# PCB-BI8-3x1.net
KiCad netlist of a schematic drawn in EAGLE
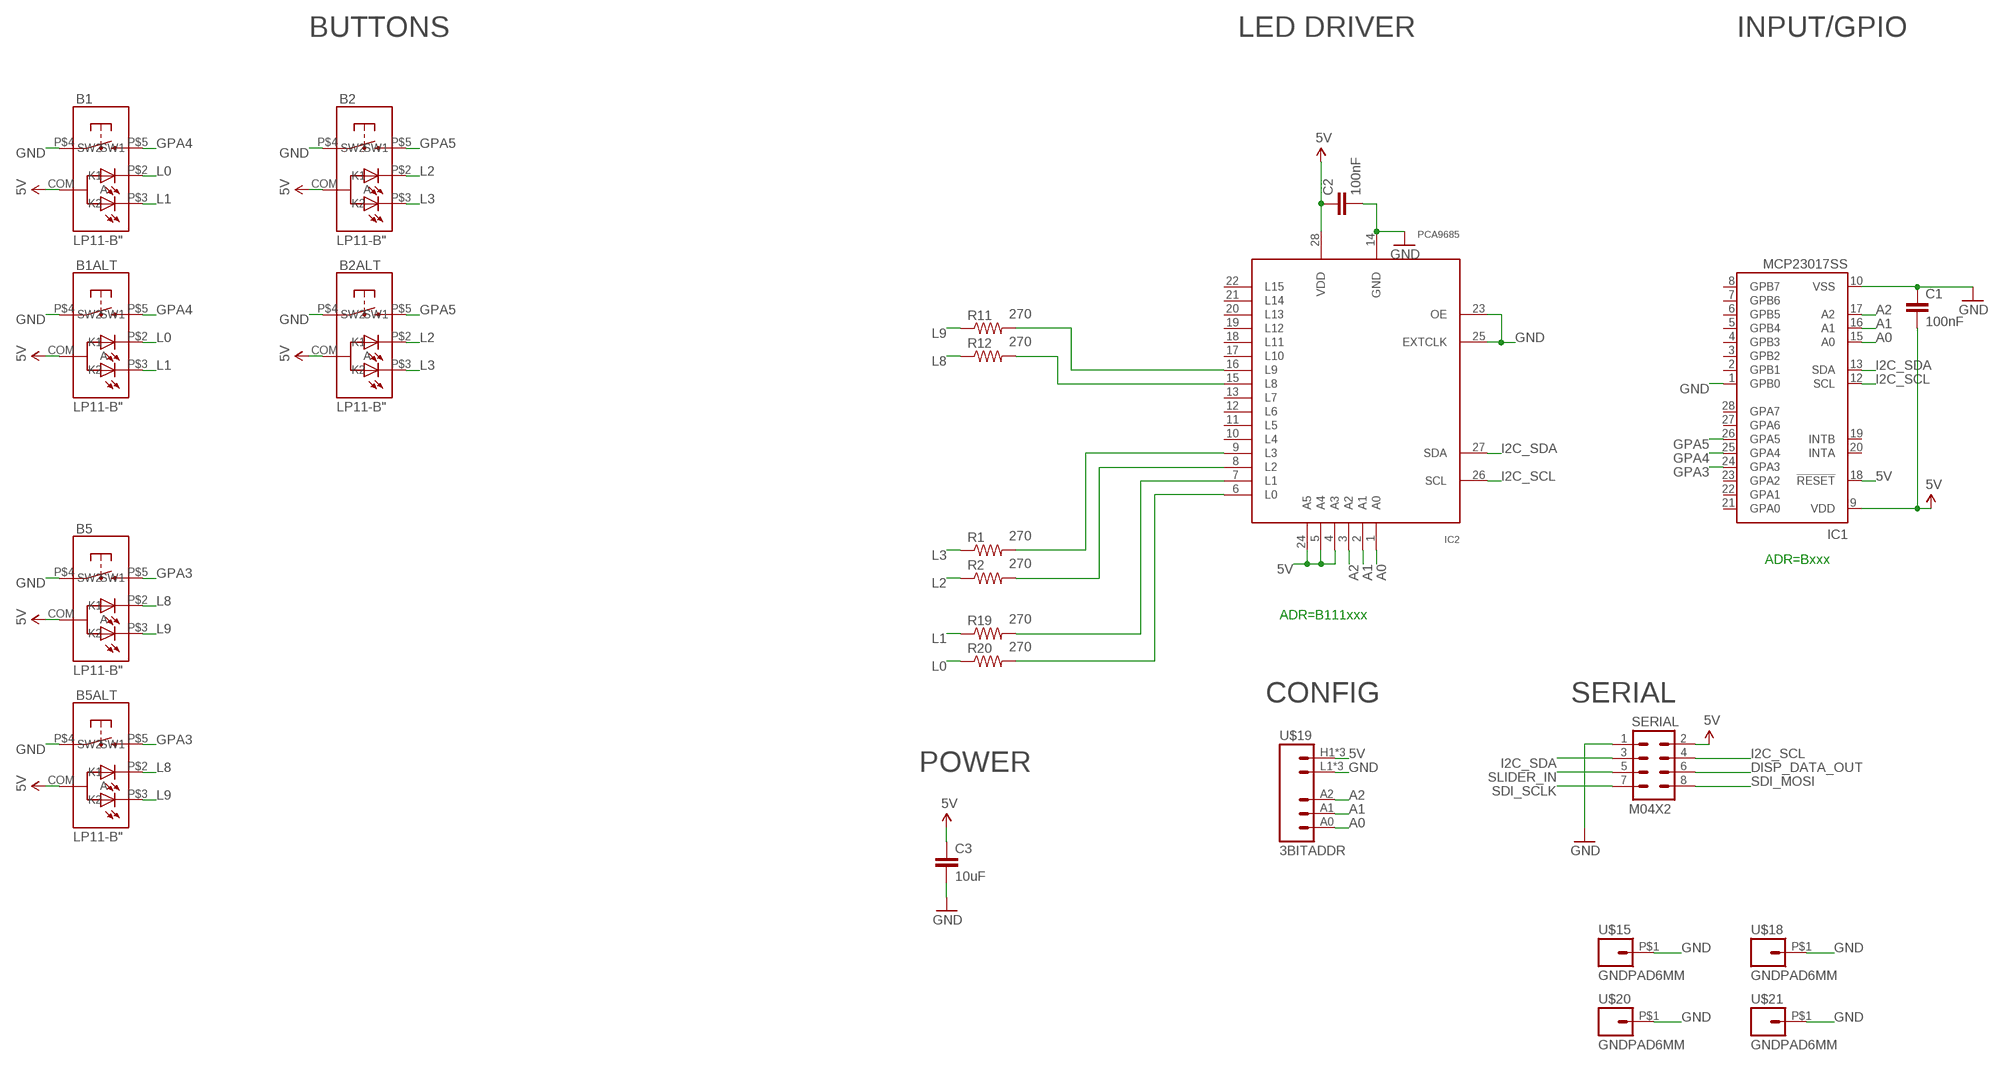
[diagram p0: schematic, sheet 1]

(export (version "E")
  (design (tool "Eeschema 10.0.6"))
  (components
    (comp (ref "B1")
      (value "LP11-B\"")
      (footprint "eagle-import:LP11")
      (libsource (lib "eagle-import") (part "LP11-B{dblquote}"))
    )
    (comp (ref "B1ALT")
      (value "LP11-B\"")
      (footprint "eagle-import:LP11")
      (libsource (lib "eagle-import") (part "LP11-B{dblquote}"))
    )
    (comp (ref "B2")
      (value "LP11-B\"")
      (footprint "eagle-import:LP11")
      (libsource (lib "eagle-import") (part "LP11-B{dblquote}"))
    )
    (comp (ref "B2ALT")
      (value "LP11-B\"")
      (footprint "eagle-import:LP11")
      (libsource (lib "eagle-import") (part "LP11-B{dblquote}"))
    )
    (comp (ref "B5")
      (value "LP11-B\"")
      (footprint "eagle-import:LP11")
      (libsource (lib "eagle-import") (part "LP11-B{dblquote}"))
    )
    (comp (ref "B5ALT")
      (value "LP11-B\"")
      (footprint "eagle-import:LP11")
      (libsource (lib "eagle-import") (part "LP11-B{dblquote}"))
    )
    (comp (ref "C1")
      (value "100nF")
      (footprint "eagle-import:0603-CAP")
      (libsource (lib "eagle-import") (part "CAP0603-CAP"))
    )
    (comp (ref "C2")
      (value "100nF")
      (footprint "eagle-import:0603-CAP")
      (libsource (lib "eagle-import") (part "CAP0603-CAP"))
    )
    (comp (ref "C3")
      (value "10uF")
      (footprint "eagle-import:0805")
      (libsource (lib "eagle-import") (part "CAP0805"))
    )
    (comp (ref "IC1")
      (value "MCP23017SS")
      (footprint "eagle-import:SSOP28")
      (fields
        (field (name "MF") "MICROCHIP")
        (field (name "MPN") "MCP23017-E/SS")
        (field (name "MPN_1") "MCP23017-E/SS")
        (field (name "OC_FARNELL") "1467674")
        (field (name "OC_NEWARK") "31K2960")
      )
      (libsource (lib "eagle-import") (part "MCP23017SS"))
    )
    (comp (ref "IC2")
      (value "PCA9685")
      (footprint "eagle-import:TSSOP28")
      (libsource (lib "eagle-import") (part "PCA9685"))
    )
    (comp (ref "R1")
      (value "270")
      (footprint "eagle-import:0603-RES")
      (libsource (lib "eagle-import") (part "RESISTOR0603-RES"))
    )
    (comp (ref "R2")
      (value "270")
      (footprint "eagle-import:0603-RES")
      (libsource (lib "eagle-import") (part "RESISTOR0603-RES"))
    )
    (comp (ref "R11")
      (value "270")
      (footprint "eagle-import:0603-RES")
      (libsource (lib "eagle-import") (part "RESISTOR0603-RES"))
    )
    (comp (ref "R12")
      (value "270")
      (footprint "eagle-import:0603-RES")
      (libsource (lib "eagle-import") (part "RESISTOR0603-RES"))
    )
    (comp (ref "R19")
      (value "270")
      (footprint "eagle-import:0603-RES")
      (libsource (lib "eagle-import") (part "RESISTOR0603-RES"))
    )
    (comp (ref "R20")
      (value "270")
      (footprint "eagle-import:0603-RES")
      (libsource (lib "eagle-import") (part "RESISTOR0603-RES"))
    )
    (comp (ref "SERIAL")
      (value "M04X2")
      (footprint "eagle-import:2X4")
      (libsource (lib "eagle-import") (part "M04X2"))
    )
    (comp (ref "U$15")
      (value "GNDPAD6MM")
      (footprint "eagle-import:3.2MMPAD6MM")
      (libsource (lib "eagle-import") (part "GNDPAD6MM"))
    )
    (comp (ref "U$18")
      (value "GNDPAD6MM")
      (footprint "eagle-import:3.2MMPAD6MM")
      (libsource (lib "eagle-import") (part "GNDPAD6MM"))
    )
    (comp (ref "U$19")
      (value "3BITADDR")
      (footprint "eagle-import:3BITADDR")
      (libsource (lib "eagle-import") (part "3BITADDR"))
    )
    (comp (ref "U$20")
      (value "GNDPAD6MM")
      (footprint "eagle-import:3.2MMPAD6MM")
      (libsource (lib "eagle-import") (part "GNDPAD6MM"))
    )
    (comp (ref "U$21")
      (value "GNDPAD6MM")
      (footprint "eagle-import:3.2MMPAD6MM")
      (libsource (lib "eagle-import") (part "GNDPAD6MM"))
    )
  )
  (nets
    (net (code "1") (name "5V") (class "Default")
      (node (ref "B1") (pin "COM") (pinfunction "A_COM") (pintype "bidirectional"))
      (node (ref "B1ALT") (pin "COM") (pinfunction "A_COM") (pintype "bidirectional"))
      (node (ref "B2") (pin "COM") (pinfunction "A_COM") (pintype "bidirectional"))
      (node (ref "B2ALT") (pin "COM") (pinfunction "A_COM") (pintype "bidirectional"))
      (node (ref "B5") (pin "COM") (pinfunction "A_COM") (pintype "bidirectional"))
      (node (ref "B5ALT") (pin "COM") (pinfunction "A_COM") (pintype "bidirectional"))
      (node (ref "C1") (pin "2") (pinfunction "2_2") (pintype "passive"))
      (node (ref "C2") (pin "1") (pinfunction "1_1") (pintype "passive"))
      (node (ref "C3") (pin "1") (pinfunction "1_1") (pintype "passive"))
      (node (ref "IC1") (pin "18") (pinfunction "~{RESET}_18") (pintype "input"))
      (node (ref "IC1") (pin "9") (pinfunction "VDD_9") (pintype "power_in"))
      (node (ref "IC2") (pin "24") (pinfunction "A5_24") (pintype "input"))
      (node (ref "IC2") (pin "28") (pinfunction "VDD_28") (pintype "power_in"))
      (node (ref "IC2") (pin "4") (pinfunction "A3_4") (pintype "input"))
      (node (ref "IC2") (pin "5") (pinfunction "A4_5") (pintype "input"))
      (node (ref "SERIAL") (pin "2") (pinfunction "2_2") (pintype "passive"))
      (node (ref "U$19") (pin "H1") (pinfunction "VCC_H1") (pintype "passive"))
      (node (ref "U$19") (pin "H2") (pinfunction "VCC_H2") (pintype "passive"))
      (node (ref "U$19") (pin "H3") (pinfunction "VCC_H3") (pintype "passive"))
    )
    (net (code "2") (name "A0") (class "Default")
      (node (ref "IC1") (pin "15") (pinfunction "A0_15") (pintype "input"))
      (node (ref "IC2") (pin "1") (pinfunction "A0_1") (pintype "input"))
      (node (ref "U$19") (pin "A0") (pinfunction "A0_A0") (pintype "passive"))
    )
    (net (code "3") (name "A1") (class "Default")
      (node (ref "IC1") (pin "16") (pinfunction "A1_16") (pintype "input"))
      (node (ref "IC2") (pin "2") (pinfunction "A1_2") (pintype "input"))
      (node (ref "U$19") (pin "A1") (pinfunction "A1_A1") (pintype "passive"))
    )
    (net (code "4") (name "A2") (class "Default")
      (node (ref "IC1") (pin "17") (pinfunction "A2_17") (pintype "input"))
      (node (ref "IC2") (pin "3") (pinfunction "A2_3") (pintype "input"))
      (node (ref "U$19") (pin "A2") (pinfunction "A2_A2") (pintype "passive"))
    )
    (net (code "5") (name "DISP_DATA_OUT") (class "Default")
      (node (ref "SERIAL") (pin "6") (pinfunction "6_6") (pintype "passive"))
    )
    (net (code "6") (name "GND") (class "Default")
      (node (ref "B1") (pin "P$4") (pinfunction "SW1_P$4") (pintype "bidirectional"))
      (node (ref "B1ALT") (pin "P$4") (pinfunction "SW1_P$4") (pintype "bidirectional"))
      (node (ref "B2") (pin "P$4") (pinfunction "SW1_P$4") (pintype "bidirectional"))
      (node (ref "B2ALT") (pin "P$4") (pinfunction "SW1_P$4") (pintype "bidirectional"))
      (node (ref "B5") (pin "P$4") (pinfunction "SW1_P$4") (pintype "bidirectional"))
      (node (ref "B5ALT") (pin "P$4") (pinfunction "SW1_P$4") (pintype "bidirectional"))
      (node (ref "C1") (pin "1") (pinfunction "1_1") (pintype "passive"))
      (node (ref "C2") (pin "2") (pinfunction "2_2") (pintype "passive"))
      (node (ref "C3") (pin "2") (pinfunction "2_2") (pintype "passive"))
      (node (ref "IC1") (pin "1") (pinfunction "GPB0_1") (pintype "bidirectional"))
      (node (ref "IC1") (pin "10") (pinfunction "VSS_10") (pintype "power_in"))
      (node (ref "IC2") (pin "14") (pinfunction "GND_14") (pintype "power_in"))
      (node (ref "IC2") (pin "23") (pinfunction "OE_23") (pintype "input"))
      (node (ref "IC2") (pin "25") (pinfunction "EXTCLK_25") (pintype "input"))
      (node (ref "SERIAL") (pin "1") (pinfunction "1_1") (pintype "passive"))
      (node (ref "U$15") (pin "P$1") (pinfunction "1_P$1") (pintype "passive"))
      (node (ref "U$18") (pin "P$1") (pinfunction "1_P$1") (pintype "passive"))
      (node (ref "U$19") (pin "L1") (pinfunction "GND_L1") (pintype "passive"))
      (node (ref "U$19") (pin "L2") (pinfunction "GND_L2") (pintype "passive"))
      (node (ref "U$19") (pin "L3") (pinfunction "GND_L3") (pintype "passive"))
      (node (ref "U$20") (pin "P$1") (pinfunction "1_P$1") (pintype "passive"))
      (node (ref "U$21") (pin "P$1") (pinfunction "1_P$1") (pintype "passive"))
    )
    (net (code "7") (name "GPA3") (class "Default")
      (node (ref "B5") (pin "P$5") (pinfunction "SW2_P$5") (pintype "bidirectional"))
      (node (ref "B5ALT") (pin "P$5") (pinfunction "SW2_P$5") (pintype "bidirectional"))
      (node (ref "IC1") (pin "24") (pinfunction "GPA3_24") (pintype "bidirectional"))
    )
    (net (code "8") (name "GPA4") (class "Default")
      (node (ref "B1") (pin "P$5") (pinfunction "SW2_P$5") (pintype "bidirectional"))
      (node (ref "B1ALT") (pin "P$5") (pinfunction "SW2_P$5") (pintype "bidirectional"))
      (node (ref "IC1") (pin "25") (pinfunction "GPA4_25") (pintype "bidirectional"))
    )
    (net (code "9") (name "GPA5") (class "Default")
      (node (ref "B2") (pin "P$5") (pinfunction "SW2_P$5") (pintype "bidirectional"))
      (node (ref "B2ALT") (pin "P$5") (pinfunction "SW2_P$5") (pintype "bidirectional"))
      (node (ref "IC1") (pin "26") (pinfunction "GPA5_26") (pintype "bidirectional"))
    )
    (net (code "10") (name "I2C_SCL") (class "Default")
      (node (ref "IC1") (pin "12") (pinfunction "SCL_12") (pintype "input"))
      (node (ref "IC2") (pin "26") (pinfunction "SCL_26") (pintype "input"))
      (node (ref "SERIAL") (pin "4") (pinfunction "4_4") (pintype "passive"))
    )
    (net (code "11") (name "I2C_SDA") (class "Default")
      (node (ref "IC1") (pin "13") (pinfunction "SDA_13") (pintype "bidirectional"))
      (node (ref "IC2") (pin "27") (pinfunction "SDA_27") (pintype "input"))
      (node (ref "SERIAL") (pin "3") (pinfunction "3_3") (pintype "passive"))
    )
    (net (code "12") (name "L0") (class "Default")
      (node (ref "B1") (pin "P$2") (pinfunction "K1_P$2") (pintype "bidirectional"))
      (node (ref "B1ALT") (pin "P$2") (pinfunction "K1_P$2") (pintype "bidirectional"))
      (node (ref "R20") (pin "1") (pinfunction "1_1") (pintype "passive"))
    )
    (net (code "13") (name "L1") (class "Default")
      (node (ref "B1") (pin "P$3") (pinfunction "K2_P$3") (pintype "bidirectional"))
      (node (ref "B1ALT") (pin "P$3") (pinfunction "K2_P$3") (pintype "bidirectional"))
      (node (ref "R19") (pin "1") (pinfunction "1_1") (pintype "passive"))
    )
    (net (code "14") (name "L2") (class "Default")
      (node (ref "B2") (pin "P$2") (pinfunction "K1_P$2") (pintype "bidirectional"))
      (node (ref "B2ALT") (pin "P$2") (pinfunction "K1_P$2") (pintype "bidirectional"))
      (node (ref "R2") (pin "1") (pinfunction "1_1") (pintype "passive"))
    )
    (net (code "15") (name "L3") (class "Default")
      (node (ref "B2") (pin "P$3") (pinfunction "K2_P$3") (pintype "bidirectional"))
      (node (ref "B2ALT") (pin "P$3") (pinfunction "K2_P$3") (pintype "bidirectional"))
      (node (ref "R1") (pin "1") (pinfunction "1_1") (pintype "passive"))
    )
    (net (code "16") (name "L8") (class "Default")
      (node (ref "B5") (pin "P$2") (pinfunction "K1_P$2") (pintype "bidirectional"))
      (node (ref "B5ALT") (pin "P$2") (pinfunction "K1_P$2") (pintype "bidirectional"))
      (node (ref "R12") (pin "1") (pinfunction "1_1") (pintype "passive"))
    )
    (net (code "17") (name "L9") (class "Default")
      (node (ref "B5") (pin "P$3") (pinfunction "K2_P$3") (pintype "bidirectional"))
      (node (ref "B5ALT") (pin "P$3") (pinfunction "K2_P$3") (pintype "bidirectional"))
      (node (ref "R11") (pin "1") (pinfunction "1_1") (pintype "passive"))
    )
    (net (code "18") (name "Net-(IC2-L0)") (class "Default")
      (node (ref "IC2") (pin "6") (pinfunction "L0_6") (pintype "output"))
      (node (ref "R20") (pin "2") (pinfunction "2_2") (pintype "passive"))
    )
    (net (code "19") (name "Net-(IC2-L1)") (class "Default")
      (node (ref "IC2") (pin "7") (pinfunction "L1_7") (pintype "output"))
      (node (ref "R19") (pin "2") (pinfunction "2_2") (pintype "passive"))
    )
    (net (code "20") (name "Net-(IC2-L2)") (class "Default")
      (node (ref "IC2") (pin "8") (pinfunction "L2_8") (pintype "output"))
      (node (ref "R2") (pin "2") (pinfunction "2_2") (pintype "passive"))
    )
    (net (code "21") (name "Net-(IC2-L3)") (class "Default")
      (node (ref "IC2") (pin "9") (pinfunction "L3_9") (pintype "output"))
      (node (ref "R1") (pin "2") (pinfunction "2_2") (pintype "passive"))
    )
    (net (code "22") (name "Net-(IC2-L8)") (class "Default")
      (node (ref "IC2") (pin "15") (pinfunction "L8_15") (pintype "output"))
      (node (ref "R12") (pin "2") (pinfunction "2_2") (pintype "passive"))
    )
    (net (code "23") (name "Net-(IC2-L9)") (class "Default")
      (node (ref "IC2") (pin "16") (pinfunction "L9_16") (pintype "output"))
      (node (ref "R11") (pin "2") (pinfunction "2_2") (pintype "passive"))
    )
    (net (code "24") (name "SDI_MOSI") (class "Default")
      (node (ref "SERIAL") (pin "8") (pinfunction "8_8") (pintype "passive"))
    )
    (net (code "25") (name "SDI_SCLK") (class "Default")
      (node (ref "SERIAL") (pin "7") (pinfunction "7_7") (pintype "passive"))
    )
    (net (code "26") (name "SLIDER_IN") (class "Default")
      (node (ref "SERIAL") (pin "5") (pinfunction "5_5") (pintype "passive"))
    )
    (net (code "27") (name "unconnected-(IC1-GPA0-Pad21)") (class "Default")
      (node (ref "IC1") (pin "21") (pinfunction "GPA0_21") (pintype "bidirectional"))
    )
    (net (code "28") (name "unconnected-(IC1-GPA1-Pad22)") (class "Default")
      (node (ref "IC1") (pin "22") (pinfunction "GPA1_22") (pintype "bidirectional"))
    )
    (net (code "29") (name "unconnected-(IC1-GPA2-Pad23)") (class "Default")
      (node (ref "IC1") (pin "23") (pinfunction "GPA2_23") (pintype "bidirectional"))
    )
    (net (code "30") (name "unconnected-(IC1-GPA6-Pad27)") (class "Default")
      (node (ref "IC1") (pin "27") (pinfunction "GPA6_27") (pintype "bidirectional"))
    )
    (net (code "31") (name "unconnected-(IC1-GPA7-Pad28)") (class "Default")
      (node (ref "IC1") (pin "28") (pinfunction "GPA7_28") (pintype "bidirectional"))
    )
    (net (code "32") (name "unconnected-(IC1-GPB1-Pad2)") (class "Default")
      (node (ref "IC1") (pin "2") (pinfunction "GPB1_2") (pintype "bidirectional"))
    )
    (net (code "33") (name "unconnected-(IC1-GPB2-Pad3)") (class "Default")
      (node (ref "IC1") (pin "3") (pinfunction "GPB2_3") (pintype "bidirectional"))
    )
    (net (code "34") (name "unconnected-(IC1-GPB3-Pad4)") (class "Default")
      (node (ref "IC1") (pin "4") (pinfunction "GPB3_4") (pintype "bidirectional"))
    )
    (net (code "35") (name "unconnected-(IC1-GPB4-Pad5)") (class "Default")
      (node (ref "IC1") (pin "5") (pinfunction "GPB4_5") (pintype "bidirectional"))
    )
    (net (code "36") (name "unconnected-(IC1-GPB5-Pad6)") (class "Default")
      (node (ref "IC1") (pin "6") (pinfunction "GPB5_6") (pintype "bidirectional"))
    )
    (net (code "37") (name "unconnected-(IC1-GPB6-Pad7)") (class "Default")
      (node (ref "IC1") (pin "7") (pinfunction "GPB6_7") (pintype "bidirectional"))
    )
    (net (code "38") (name "unconnected-(IC1-GPB7-Pad8)") (class "Default")
      (node (ref "IC1") (pin "8") (pinfunction "GPB7_8") (pintype "bidirectional"))
    )
    (net (code "39") (name "unconnected-(IC1-INTA-Pad20)") (class "Default")
      (node (ref "IC1") (pin "20") (pinfunction "INTA_20") (pintype "output"))
    )
    (net (code "40") (name "unconnected-(IC1-INTB-Pad19)") (class "Default")
      (node (ref "IC1") (pin "19") (pinfunction "INTB_19") (pintype "output"))
    )
    (net (code "41") (name "unconnected-(IC2-L4-Pad10)") (class "Default")
      (node (ref "IC2") (pin "10") (pinfunction "L4_10") (pintype "output"))
    )
    (net (code "42") (name "unconnected-(IC2-L5-Pad11)") (class "Default")
      (node (ref "IC2") (pin "11") (pinfunction "L5_11") (pintype "output"))
    )
    (net (code "43") (name "unconnected-(IC2-L6-Pad12)") (class "Default")
      (node (ref "IC2") (pin "12") (pinfunction "L6_12") (pintype "output"))
    )
    (net (code "44") (name "unconnected-(IC2-L7-Pad13)") (class "Default")
      (node (ref "IC2") (pin "13") (pinfunction "L7_13") (pintype "output"))
    )
    (net (code "45") (name "unconnected-(IC2-L10-Pad17)") (class "Default")
      (node (ref "IC2") (pin "17") (pinfunction "L10_17") (pintype "output"))
    )
    (net (code "46") (name "unconnected-(IC2-L11-Pad18)") (class "Default")
      (node (ref "IC2") (pin "18") (pinfunction "L11_18") (pintype "output"))
    )
    (net (code "47") (name "unconnected-(IC2-L12-Pad19)") (class "Default")
      (node (ref "IC2") (pin "19") (pinfunction "L12_19") (pintype "output"))
    )
    (net (code "48") (name "unconnected-(IC2-L13-Pad20)") (class "Default")
      (node (ref "IC2") (pin "20") (pinfunction "L13_20") (pintype "output"))
    )
    (net (code "49") (name "unconnected-(IC2-L14-Pad21)") (class "Default")
      (node (ref "IC2") (pin "21") (pinfunction "L14_21") (pintype "output"))
    )
    (net (code "50") (name "unconnected-(IC2-L15-Pad22)") (class "Default")
      (node (ref "IC2") (pin "22") (pinfunction "L15_22") (pintype "output"))
    )
  )
)
